# main_V1.net
KiCad netlist of a schematic drawn in EAGLE
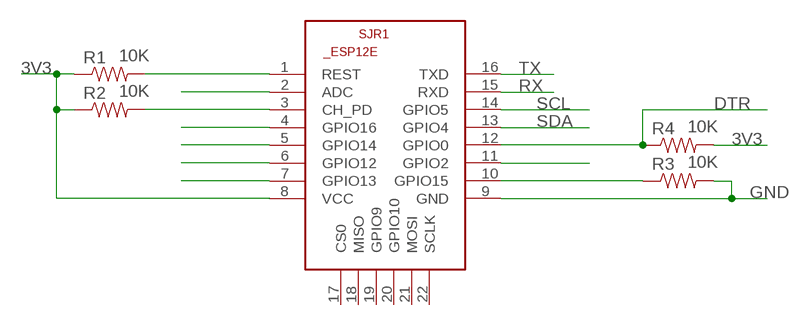
[diagram p0: schematic, sheet 1]
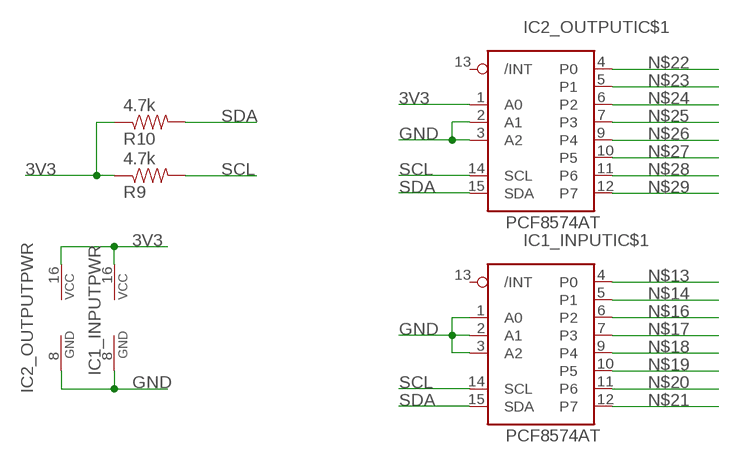
[diagram p1: schematic, sheet 2]
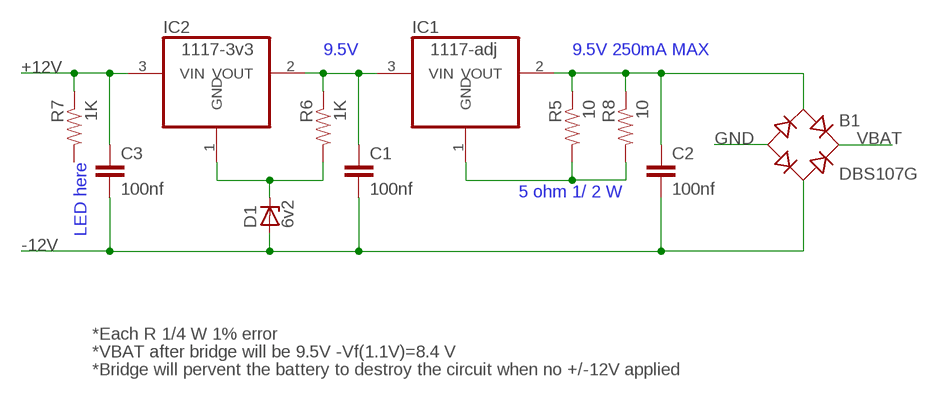
[diagram p2: schematic, sheet 3]
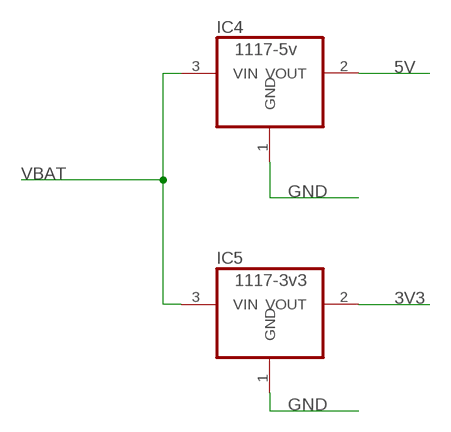
[diagram p3: schematic, sheet 4]
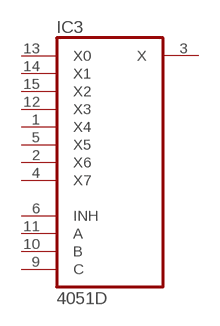
[diagram p4: schematic, sheet 5]

(export (version "E")
  (design (tool "Eeschema 10.0.6"))
  (components
    (comp (ref "B1")
      (value "DBS107G")
      (footprint "eagle-import:DBS")
      (libsource (lib "eagle-import") (part "DB?GS107"))
    )
    (comp (ref "C1")
      (value "100nf")
      (footprint "eagle-import:C1206K")
      (libsource (lib "eagle-import") (part "C-EUC1206K"))
    )
    (comp (ref "C2")
      (value "100nf")
      (footprint "eagle-import:C1206K")
      (libsource (lib "eagle-import") (part "C-EUC1206K"))
    )
    (comp (ref "C3")
      (value "100nf")
      (footprint "eagle-import:C1206K")
      (libsource (lib "eagle-import") (part "C-EUC1206K"))
    )
    (comp (ref "D1")
      (value "6v2")
      (footprint "eagle-import:SOT23")
      (libsource (lib "eagle-import") (part "ZENER-DIODESOT23"))
    )
    (comp (ref "IC1")
      (value "1117-adj")
      (footprint "eagle-import:SOT223")
      (fields (field (name "MPN") "REG1117"))
      (libsource (lib "eagle-import") (part "REG1117"))
    )
    (comp (ref "IC2")
      (value "1117-3v3")
      (footprint "eagle-import:SOT223")
      (fields (field (name "MPN") "REG1117"))
      (libsource (lib "eagle-import") (part "REG1117"))
    )
    (comp (ref "R5")
      (value "10")
      (footprint "eagle-import:1206")
      (libsource (lib "eagle-import") (part "RESISTOR1206"))
    )
    (comp (ref "R6")
      (value "1K")
      (footprint "eagle-import:1206")
      (libsource (lib "eagle-import") (part "RESISTOR1206"))
    )
    (comp (ref "R7")
      (value "1K")
      (footprint "eagle-import:1206")
      (libsource (lib "eagle-import") (part "RESISTOR1206"))
    )
    (comp (ref "R8")
      (value "10")
      (footprint "eagle-import:1206")
      (libsource (lib "eagle-import") (part "RESISTOR1206"))
    )
    (comp (ref "IC4")
      (value "1117-5v")
      (footprint "eagle-import:SOT223")
      (fields (field (name "MPN") "REG1117"))
      (libsource (lib "eagle-import") (part "REG1117"))
    )
    (comp (ref "IC5")
      (value "1117-3v3")
      (footprint "eagle-import:SOT223")
      (fields (field (name "MPN") "REG1117"))
      (libsource (lib "eagle-import") (part "REG1117"))
    )
    (comp (ref "R1")
      (value "10K")
      (footprint "eagle-import:1206")
      (libsource (lib "eagle-import") (part "RESISTOR1206"))
    )
    (comp (ref "R2")
      (value "10K")
      (footprint "eagle-import:1206")
      (libsource (lib "eagle-import") (part "RESISTOR1206"))
    )
    (comp (ref "R3")
      (value "10K")
      (footprint "eagle-import:1206")
      (libsource (lib "eagle-import") (part "RESISTOR1206"))
    )
    (comp (ref "R4")
      (value "10K")
      (footprint "eagle-import:1206")
      (libsource (lib "eagle-import") (part "RESISTOR1206"))
    )
    (comp (ref "SJR1")
      (value "ESP8266-12EESP12E")
      (footprint "eagle-import:ESP8266-ESP12E")
      (libsource (lib "eagle-import") (part "ESP8266-12EESP12E"))
    )
    (comp (ref "IC3")
      (value "4051D")
      (footprint "eagle-import:SO16")
      (libsource (lib "eagle-import") (part "4051D"))
    )
    (comp (ref "IC1_INPUT")
      (value "PCF8574AT")
      (footprint "eagle-import:SO16")
      (libsource (lib "eagle-import") (part "PCF8574AT"))
    )
    (comp (ref "IC2_OUTPUT")
      (value "PCF8574AT")
      (footprint "eagle-import:SO16")
      (libsource (lib "eagle-import") (part "PCF8574AT"))
    )
    (comp (ref "R9")
      (value "4.7k")
      (footprint "eagle-import:1206")
      (libsource (lib "eagle-import") (part "RESISTOR1206"))
    )
    (comp (ref "R10")
      (value "4.7k")
      (footprint "eagle-import:1206")
      (libsource (lib "eagle-import") (part "RESISTOR1206"))
    )
  )
  (nets
    (net (code "1") (name "+12V") (class "Default")
      (node (ref "C3") (pin "1") (pinfunction "1_1") (pintype "passive"))
      (node (ref "IC2") (pin "3") (pinfunction "VIN_3") (pintype "input"))
      (node (ref "R7") (pin "1") (pinfunction "1_1") (pintype "passive"))
    )
    (net (code "2") (name "-12V") (class "Default")
      (node (ref "B1") (pin "AC2") (pinfunction "AC2_AC2") (pintype "passive"))
      (node (ref "C1") (pin "2") (pinfunction "2_2") (pintype "passive"))
      (node (ref "C2") (pin "2") (pinfunction "2_2") (pintype "passive"))
      (node (ref "C3") (pin "2") (pinfunction "2_2") (pintype "passive"))
      (node (ref "D1") (pin "1") (pinfunction "A_1") (pintype "passive"))
    )
    (net (code "3") (name "3V3") (class "Default")
      (node (ref "IC1_INPUT") (pin "16") (pinfunction "VCC_16") (pintype "power_in"))
      (node (ref "IC2_OUTPUT") (pin "1") (pinfunction "A0_1") (pintype "input"))
      (node (ref "IC2_OUTPUT") (pin "16") (pinfunction "VCC_16") (pintype "power_in"))
      (node (ref "IC5") (pin "2") (pinfunction "VOUT_2") (pintype "output"))
      (node (ref "R1") (pin "1") (pinfunction "1_1") (pintype "passive"))
      (node (ref "R10") (pin "1") (pinfunction "1_1") (pintype "passive"))
      (node (ref "R2") (pin "1") (pinfunction "1_1") (pintype "passive"))
      (node (ref "R4") (pin "2") (pinfunction "2_2") (pintype "passive"))
      (node (ref "R9") (pin "1") (pinfunction "1_1") (pintype "passive"))
      (node (ref "SJR1") (pin "8") (pinfunction "VCC_8") (pintype "bidirectional"))
    )
    (net (code "4") (name "5V") (class "Default")
      (node (ref "IC4") (pin "2") (pinfunction "VOUT_2") (pintype "output"))
    )
    (net (code "5") (name "DTR") (class "Default")
      (node (ref "R4") (pin "1") (pinfunction "1_1") (pintype "passive"))
      (node (ref "SJR1") (pin "12") (pinfunction "GPIO0_12") (pintype "bidirectional"))
    )
    (net (code "6") (name "GND") (class "Default")
      (node (ref "B1") (pin "-") (pinfunction "-_-") (pintype "passive"))
      (node (ref "IC1_INPUT") (pin "1") (pinfunction "A0_1") (pintype "input"))
      (node (ref "IC1_INPUT") (pin "2") (pinfunction "A1_2") (pintype "input"))
      (node (ref "IC1_INPUT") (pin "3") (pinfunction "A2_3") (pintype "input"))
      (node (ref "IC1_INPUT") (pin "8") (pinfunction "GND_8") (pintype "power_in"))
      (node (ref "IC2_OUTPUT") (pin "2") (pinfunction "A1_2") (pintype "input"))
      (node (ref "IC2_OUTPUT") (pin "3") (pinfunction "A2_3") (pintype "input"))
      (node (ref "IC2_OUTPUT") (pin "8") (pinfunction "GND_8") (pintype "power_in"))
      (node (ref "IC4") (pin "1") (pinfunction "GND_1") (pintype "power_in"))
      (node (ref "IC5") (pin "1") (pinfunction "GND_1") (pintype "power_in"))
      (node (ref "R3") (pin "2") (pinfunction "2_2") (pintype "passive"))
      (node (ref "SJR1") (pin "9") (pinfunction "GND_9") (pintype "bidirectional"))
    )
    (net (code "7") (name "N$13") (class "Default")
      (node (ref "IC1_INPUT") (pin "4") (pinfunction "P0_4") (pintype "bidirectional"))
    )
    (net (code "8") (name "N$14") (class "Default")
      (node (ref "IC1_INPUT") (pin "5") (pinfunction "P1_5") (pintype "bidirectional"))
    )
    (net (code "9") (name "N$16") (class "Default")
      (node (ref "IC1_INPUT") (pin "6") (pinfunction "P2_6") (pintype "bidirectional"))
    )
    (net (code "10") (name "N$17") (class "Default")
      (node (ref "IC1_INPUT") (pin "7") (pinfunction "P3_7") (pintype "bidirectional"))
    )
    (net (code "11") (name "N$18") (class "Default")
      (node (ref "IC1_INPUT") (pin "9") (pinfunction "P4_9") (pintype "bidirectional"))
    )
    (net (code "12") (name "N$19") (class "Default")
      (node (ref "IC1_INPUT") (pin "10") (pinfunction "P5_10") (pintype "bidirectional"))
    )
    (net (code "13") (name "N$20") (class "Default")
      (node (ref "IC1_INPUT") (pin "11") (pinfunction "P6_11") (pintype "bidirectional"))
    )
    (net (code "14") (name "N$21") (class "Default")
      (node (ref "IC1_INPUT") (pin "12") (pinfunction "P7_12") (pintype "bidirectional"))
    )
    (net (code "15") (name "N$22") (class "Default")
      (node (ref "IC2_OUTPUT") (pin "4") (pinfunction "P0_4") (pintype "bidirectional"))
    )
    (net (code "16") (name "N$23") (class "Default")
      (node (ref "IC2_OUTPUT") (pin "5") (pinfunction "P1_5") (pintype "bidirectional"))
    )
    (net (code "17") (name "N$24") (class "Default")
      (node (ref "IC2_OUTPUT") (pin "6") (pinfunction "P2_6") (pintype "bidirectional"))
    )
    (net (code "18") (name "N$25") (class "Default")
      (node (ref "IC2_OUTPUT") (pin "7") (pinfunction "P3_7") (pintype "bidirectional"))
    )
    (net (code "19") (name "N$26") (class "Default")
      (node (ref "IC2_OUTPUT") (pin "9") (pinfunction "P4_9") (pintype "bidirectional"))
    )
    (net (code "20") (name "N$27") (class "Default")
      (node (ref "IC2_OUTPUT") (pin "10") (pinfunction "P5_10") (pintype "bidirectional"))
    )
    (net (code "21") (name "N$28") (class "Default")
      (node (ref "IC2_OUTPUT") (pin "11") (pinfunction "P6_11") (pintype "bidirectional"))
    )
    (net (code "22") (name "N$29") (class "Default")
      (node (ref "IC2_OUTPUT") (pin "12") (pinfunction "P7_12") (pintype "bidirectional"))
    )
    (net (code "23") (name "Net-(D1-C)") (class "Default")
      (node (ref "D1") (pin "3") (pinfunction "C_3") (pintype "passive"))
      (node (ref "IC2") (pin "1") (pinfunction "GND_1") (pintype "power_in"))
      (node (ref "R6") (pin "2") (pinfunction "2_2") (pintype "passive"))
    )
    (net (code "24") (name "Net-(IC1-GND)") (class "Default")
      (node (ref "IC1") (pin "1") (pinfunction "GND_1") (pintype "power_in"))
      (node (ref "R5") (pin "2") (pinfunction "2_2") (pintype "passive"))
      (node (ref "R8") (pin "2") (pinfunction "2_2") (pintype "passive"))
    )
    (net (code "25") (name "Net-(IC1-VIN)") (class "Default")
      (node (ref "C1") (pin "1") (pinfunction "1_1") (pintype "passive"))
      (node (ref "IC1") (pin "3") (pinfunction "VIN_3") (pintype "input"))
      (node (ref "IC2") (pin "2") (pinfunction "VOUT_2") (pintype "output"))
      (node (ref "R6") (pin "1") (pinfunction "1_1") (pintype "passive"))
    )
    (net (code "26") (name "Net-(IC1-VOUT)") (class "Default")
      (node (ref "B1") (pin "AC1") (pinfunction "AC1_AC1") (pintype "passive"))
      (node (ref "C2") (pin "1") (pinfunction "1_1") (pintype "passive"))
      (node (ref "IC1") (pin "2") (pinfunction "VOUT_2") (pintype "output"))
      (node (ref "R5") (pin "1") (pinfunction "1_1") (pintype "passive"))
      (node (ref "R8") (pin "1") (pinfunction "1_1") (pintype "passive"))
    )
    (net (code "27") (name "Net-(SJR1-CH_PD)") (class "Default")
      (node (ref "R2") (pin "2") (pinfunction "2_2") (pintype "passive"))
      (node (ref "SJR1") (pin "3") (pinfunction "CH_PD_3") (pintype "bidirectional"))
    )
    (net (code "28") (name "Net-(SJR1-GPIO15)") (class "Default")
      (node (ref "R3") (pin "1") (pinfunction "1_1") (pintype "passive"))
      (node (ref "SJR1") (pin "10") (pinfunction "GPIO15_10") (pintype "bidirectional"))
    )
    (net (code "29") (name "Net-(SJR1-REST)") (class "Default")
      (node (ref "R1") (pin "2") (pinfunction "2_2") (pintype "passive"))
      (node (ref "SJR1") (pin "1") (pinfunction "REST_1") (pintype "bidirectional"))
    )
    (net (code "30") (name "RX") (class "Default")
      (node (ref "SJR1") (pin "15") (pinfunction "RXD_15") (pintype "bidirectional"))
    )
    (net (code "31") (name "SCL") (class "Default")
      (node (ref "IC1_INPUT") (pin "14") (pinfunction "SCL_14") (pintype "input"))
      (node (ref "IC2_OUTPUT") (pin "14") (pinfunction "SCL_14") (pintype "input"))
      (node (ref "R9") (pin "2") (pinfunction "2_2") (pintype "passive"))
      (node (ref "SJR1") (pin "14") (pinfunction "GPIO5_14") (pintype "bidirectional"))
    )
    (net (code "32") (name "SDA") (class "Default")
      (node (ref "IC1_INPUT") (pin "15") (pinfunction "SDA_15") (pintype "bidirectional"))
      (node (ref "IC2_OUTPUT") (pin "15") (pinfunction "SDA_15") (pintype "bidirectional"))
      (node (ref "R10") (pin "2") (pinfunction "2_2") (pintype "passive"))
      (node (ref "SJR1") (pin "13") (pinfunction "GPIO4_13") (pintype "bidirectional"))
    )
    (net (code "33") (name "TX") (class "Default")
      (node (ref "SJR1") (pin "16") (pinfunction "TXD_16") (pintype "bidirectional"))
    )
    (net (code "34") (name "VBAT") (class "Default")
      (node (ref "B1") (pin "+") (pinfunction "+_+") (pintype "passive"))
      (node (ref "IC4") (pin "3") (pinfunction "VIN_3") (pintype "input"))
      (node (ref "IC5") (pin "3") (pinfunction "VIN_3") (pintype "input"))
    )
    (net (code "35") (name "unconnected-(IC1_INPUTA-{slash}INT-Pad13)") (class "Default")
      (node (ref "IC1_INPUT") (pin "13") (pinfunction "/INT_13") (pintype "output"))
    )
    (net (code "36") (name "unconnected-(IC2_OUTPUTA-{slash}INT-Pad13)") (class "Default")
      (node (ref "IC2_OUTPUT") (pin "13") (pinfunction "/INT_13") (pintype "output"))
    )
    (net (code "37") (name "unconnected-(IC3A-A-Pad11)") (class "Default")
      (node (ref "IC3") (pin "11") (pinfunction "A_11") (pintype "input"))
    )
    (net (code "38") (name "unconnected-(IC3A-B-Pad10)") (class "Default")
      (node (ref "IC3") (pin "10") (pinfunction "B_10") (pintype "input"))
    )
    (net (code "39") (name "unconnected-(IC3A-C-Pad9)") (class "Default")
      (node (ref "IC3") (pin "9") (pinfunction "C_9") (pintype "input"))
    )
    (net (code "40") (name "unconnected-(IC3A-INH-Pad6)") (class "Default")
      (node (ref "IC3") (pin "6") (pinfunction "INH_6") (pintype "input"))
    )
    (net (code "41") (name "unconnected-(IC3A-X-Pad3)") (class "Default")
      (node (ref "IC3") (pin "3") (pinfunction "X_3") (pintype "bidirectional"))
    )
    (net (code "42") (name "unconnected-(IC3A-X0-Pad13)") (class "Default")
      (node (ref "IC3") (pin "13") (pinfunction "X0_13") (pintype "bidirectional"))
    )
    (net (code "43") (name "unconnected-(IC3A-X1-Pad14)") (class "Default")
      (node (ref "IC3") (pin "14") (pinfunction "X1_14") (pintype "bidirectional"))
    )
    (net (code "44") (name "unconnected-(IC3A-X2-Pad15)") (class "Default")
      (node (ref "IC3") (pin "15") (pinfunction "X2_15") (pintype "bidirectional"))
    )
    (net (code "45") (name "unconnected-(IC3A-X3-Pad12)") (class "Default")
      (node (ref "IC3") (pin "12") (pinfunction "X3_12") (pintype "bidirectional"))
    )
    (net (code "46") (name "unconnected-(IC3A-X4-Pad1)") (class "Default")
      (node (ref "IC3") (pin "1") (pinfunction "X4_1") (pintype "bidirectional"))
    )
    (net (code "47") (name "unconnected-(IC3A-X5-Pad5)") (class "Default")
      (node (ref "IC3") (pin "5") (pinfunction "X5_5") (pintype "bidirectional"))
    )
    (net (code "48") (name "unconnected-(IC3A-X6-Pad2)") (class "Default")
      (node (ref "IC3") (pin "2") (pinfunction "X6_2") (pintype "bidirectional"))
    )
    (net (code "49") (name "unconnected-(IC3A-X7-Pad4)") (class "Default")
      (node (ref "IC3") (pin "4") (pinfunction "X7_4") (pintype "bidirectional"))
    )
    (net (code "50") (name "unconnected-(R7-Pad2)") (class "Default")
      (node (ref "R7") (pin "2") (pinfunction "2_2") (pintype "passive"))
    )
    (net (code "51") (name "unconnected-(SJR1-ADC-Pad2)") (class "Default")
      (node (ref "SJR1") (pin "2") (pinfunction "ADC_2") (pintype "bidirectional"))
    )
    (net (code "52") (name "unconnected-(SJR1-CS0-Pad17)") (class "Default")
      (node (ref "SJR1") (pin "17") (pinfunction "CS0_17") (pintype "bidirectional"))
    )
    (net (code "53") (name "unconnected-(SJR1-GPIO2-Pad11)") (class "Default")
      (node (ref "SJR1") (pin "11") (pinfunction "GPIO2_11") (pintype "bidirectional"))
    )
    (net (code "54") (name "unconnected-(SJR1-GPIO9-Pad19)") (class "Default")
      (node (ref "SJR1") (pin "19") (pinfunction "GPIO9_19") (pintype "bidirectional"))
    )
    (net (code "55") (name "unconnected-(SJR1-GPIO10-Pad20)") (class "Default")
      (node (ref "SJR1") (pin "20") (pinfunction "GPIO10_20") (pintype "bidirectional"))
    )
    (net (code "56") (name "unconnected-(SJR1-GPIO12-Pad6)") (class "Default")
      (node (ref "SJR1") (pin "6") (pinfunction "GPIO12_6") (pintype "bidirectional"))
    )
    (net (code "57") (name "unconnected-(SJR1-GPIO13-Pad7)") (class "Default")
      (node (ref "SJR1") (pin "7") (pinfunction "GPIO13_7") (pintype "bidirectional"))
    )
    (net (code "58") (name "unconnected-(SJR1-GPIO14-Pad5)") (class "Default")
      (node (ref "SJR1") (pin "5") (pinfunction "GPIO14_5") (pintype "bidirectional"))
    )
    (net (code "59") (name "unconnected-(SJR1-GPIO16-Pad4)") (class "Default")
      (node (ref "SJR1") (pin "4") (pinfunction "GPIO16_4") (pintype "bidirectional"))
    )
    (net (code "60") (name "unconnected-(SJR1-MISO-Pad18)") (class "Default")
      (node (ref "SJR1") (pin "18") (pinfunction "MISO_18") (pintype "bidirectional"))
    )
    (net (code "61") (name "unconnected-(SJR1-MOSI-Pad21)") (class "Default")
      (node (ref "SJR1") (pin "21") (pinfunction "MOSI_21") (pintype "bidirectional"))
    )
    (net (code "62") (name "unconnected-(SJR1-SCLK-Pad22)") (class "Default")
      (node (ref "SJR1") (pin "22") (pinfunction "SCLK_22") (pintype "bidirectional"))
    )
  )
)
